# LoRaB.net
KiCad netlist of a schematic drawn in Altium Designer
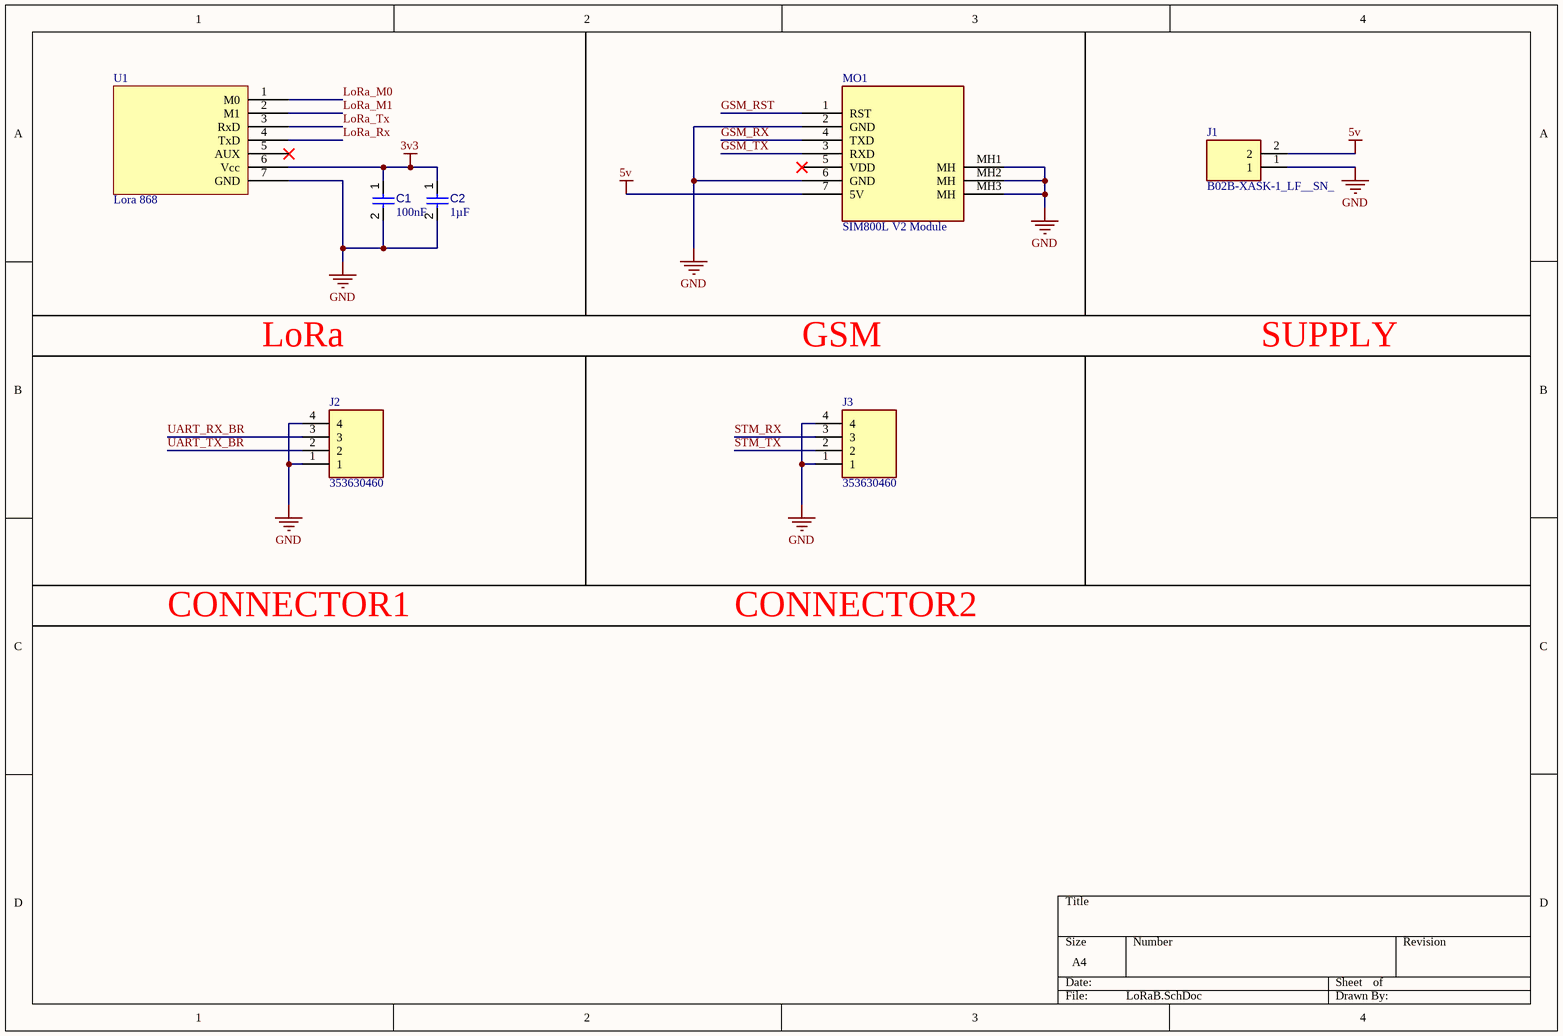
[diagram p0: LoRaB.SchDoc]

(export (version "E")
  (design (tool "Eeschema 10.0.6"))
  (components
    (comp (ref "C1")
      (value "100nF")
      (footprint "CAPC1608X90X40NL10T20")
      (description "Chip Capacitor, 100 nF, +/- 10%, 50 V, 0603 (1608 Metric)")
      (fields (field (name "TOLERANCE") "10%") (field (name "Comment") "Capacitor 100 nF +/-10% 50 V 0603"))
      (libsource (lib "Shlok Sharma") (part "CAP-NP-2"))
    )
    (comp (ref "C2")
      (value "1µF")
      (footprint "CAPC2013X135X45NL10T25")
      (description "Chip Capacitor, 1 uF, +/- 10%, 50 V, 0805 (2012 Metric)")
      (fields (field (name "TOLERANCE") "10%") (field (name "Comment") "Capacitor 1 uF +/- 10% 50 V 0805"))
      (libsource (lib "Shlok Sharma") (part "CAP-NP-2"))
    )
    (comp (ref "J1")
      (value "B02B-XASK-1_LF__SN_")
      (footprint "SamacSys:SHDR2W60P0X250_1X2_750X640X880P")
      (description "Connector")
      (fields (field (name "MANUFACTURER_PART_NUMBER") "B02B-XASK-1(LF)(SN)"))
      (libsource (lib "*") (part "B02B-XASK-1_LF__SN_"))
    )
    (comp (ref "J2")
      (value "353630460")
      (footprint "SamacSys:353630460")
      (description "Connector")
      (libsource (lib "*") (part "353630460"))
    )
    (comp (ref "J3")
      (value "353630460")
      (footprint "SamacSys:353630460")
      (description "Connector")
      (libsource (lib "*") (part "353630460"))
    )
    (comp (ref "MO1")
      (value "SIM800L V2 Module")
      (footprint "SIM800LV2.0")
      (description "GSM Module")
      (libsource (lib "rf_components") (part "SIM800LV2.0"))
    )
    (comp (ref "U1")
      (value "Lora 868")
      (footprint "Lora 833")
      (libsource (lib "rf_components") (part "Lora 833"))
    )
  )
  (nets
    (net (code "1") (name "/GSM_RST") (class "Default")
      (node (ref "MO1") (pin "1") (pinfunction "RST_1") (pintype "passive"))
    )
    (net (code "2") (name "/GSM_RX") (class "Default")
      (node (ref "MO1") (pin "4") (pinfunction "TXD_4") (pintype "passive"))
    )
    (net (code "3") (name "/GSM_TX") (class "Default")
      (node (ref "MO1") (pin "3") (pinfunction "RXD_3") (pintype "passive"))
    )
    (net (code "4") (name "/LoRa_M0") (class "Default")
      (node (ref "U1") (pin "1") (pinfunction "M0_1") (pintype "passive"))
    )
    (net (code "5") (name "/LoRa_M1") (class "Default")
      (node (ref "U1") (pin "2") (pinfunction "M1_2") (pintype "passive"))
    )
    (net (code "6") (name "/LoRa_Rx") (class "Default")
      (node (ref "U1") (pin "4") (pinfunction "TxD_4") (pintype "passive"))
    )
    (net (code "7") (name "/LoRa_Tx") (class "Default")
      (node (ref "U1") (pin "3") (pinfunction "RxD_3") (pintype "passive"))
    )
    (net (code "8") (name "/STM_RX") (class "Default")
      (node (ref "J3") (pin "3") (pinfunction "3_3") (pintype "passive"))
    )
    (net (code "9") (name "/STM_TX") (class "Default")
      (node (ref "J3") (pin "2") (pinfunction "2_2") (pintype "passive"))
    )
    (net (code "10") (name "/UART_RX_BR") (class "Default")
      (node (ref "J2") (pin "3") (pinfunction "3_3") (pintype "passive"))
    )
    (net (code "11") (name "/UART_TX_BR") (class "Default")
      (node (ref "J2") (pin "2") (pinfunction "2_2") (pintype "passive"))
    )
    (net (code "12") (name "3v3") (class "Default")
      (node (ref "C1") (pin "1") (pinfunction "1_1") (pintype "passive"))
      (node (ref "C2") (pin "1") (pinfunction "1_1") (pintype "passive"))
      (node (ref "U1") (pin "6") (pinfunction "Vcc_6") (pintype "passive"))
    )
    (net (code "13") (name "5v") (class "Default")
      (node (ref "J1") (pin "2") (pinfunction "2_2") (pintype "passive"))
      (node (ref "MO1") (pin "7") (pinfunction "5V_7") (pintype "passive"))
    )
    (net (code "14") (name "GND") (class "Default")
      (node (ref "C1") (pin "2") (pinfunction "2_2") (pintype "passive"))
      (node (ref "C2") (pin "2") (pinfunction "2_2") (pintype "passive"))
      (node (ref "J1") (pin "1") (pinfunction "1_1") (pintype "passive"))
      (node (ref "J2") (pin "1") (pinfunction "1_1") (pintype "passive"))
      (node (ref "J2") (pin "4") (pinfunction "4_4") (pintype "passive"))
      (node (ref "J3") (pin "1") (pinfunction "1_1") (pintype "passive"))
      (node (ref "J3") (pin "4") (pinfunction "4_4") (pintype "passive"))
      (node (ref "MO1") (pin "2") (pinfunction "GND_2") (pintype "passive"))
      (node (ref "MO1") (pin "6") (pinfunction "GND_6") (pintype "passive"))
      (node (ref "MO1") (pin "MH1") (pinfunction "MH_MH1") (pintype "passive"))
      (node (ref "MO1") (pin "MH2") (pinfunction "MH_MH2") (pintype "passive"))
      (node (ref "MO1") (pin "MH3") (pinfunction "MH_MH3") (pintype "passive"))
      (node (ref "U1") (pin "7") (pinfunction "GND_7") (pintype "passive"))
    )
    (net (code "15") (name "unconnected-(MO1-VDD-Pad5)") (class "Default")
      (node (ref "MO1") (pin "5") (pinfunction "VDD_5") (pintype "passive+no_connect"))
    )
    (net (code "16") (name "unconnected-(U1-AUX-Pad5)") (class "Default")
      (node (ref "U1") (pin "5") (pinfunction "AUX_5") (pintype "passive+no_connect"))
    )
  )
)
